# RAMPSdisplay.net
KiCad netlist of a schematic drawn in EAGLE
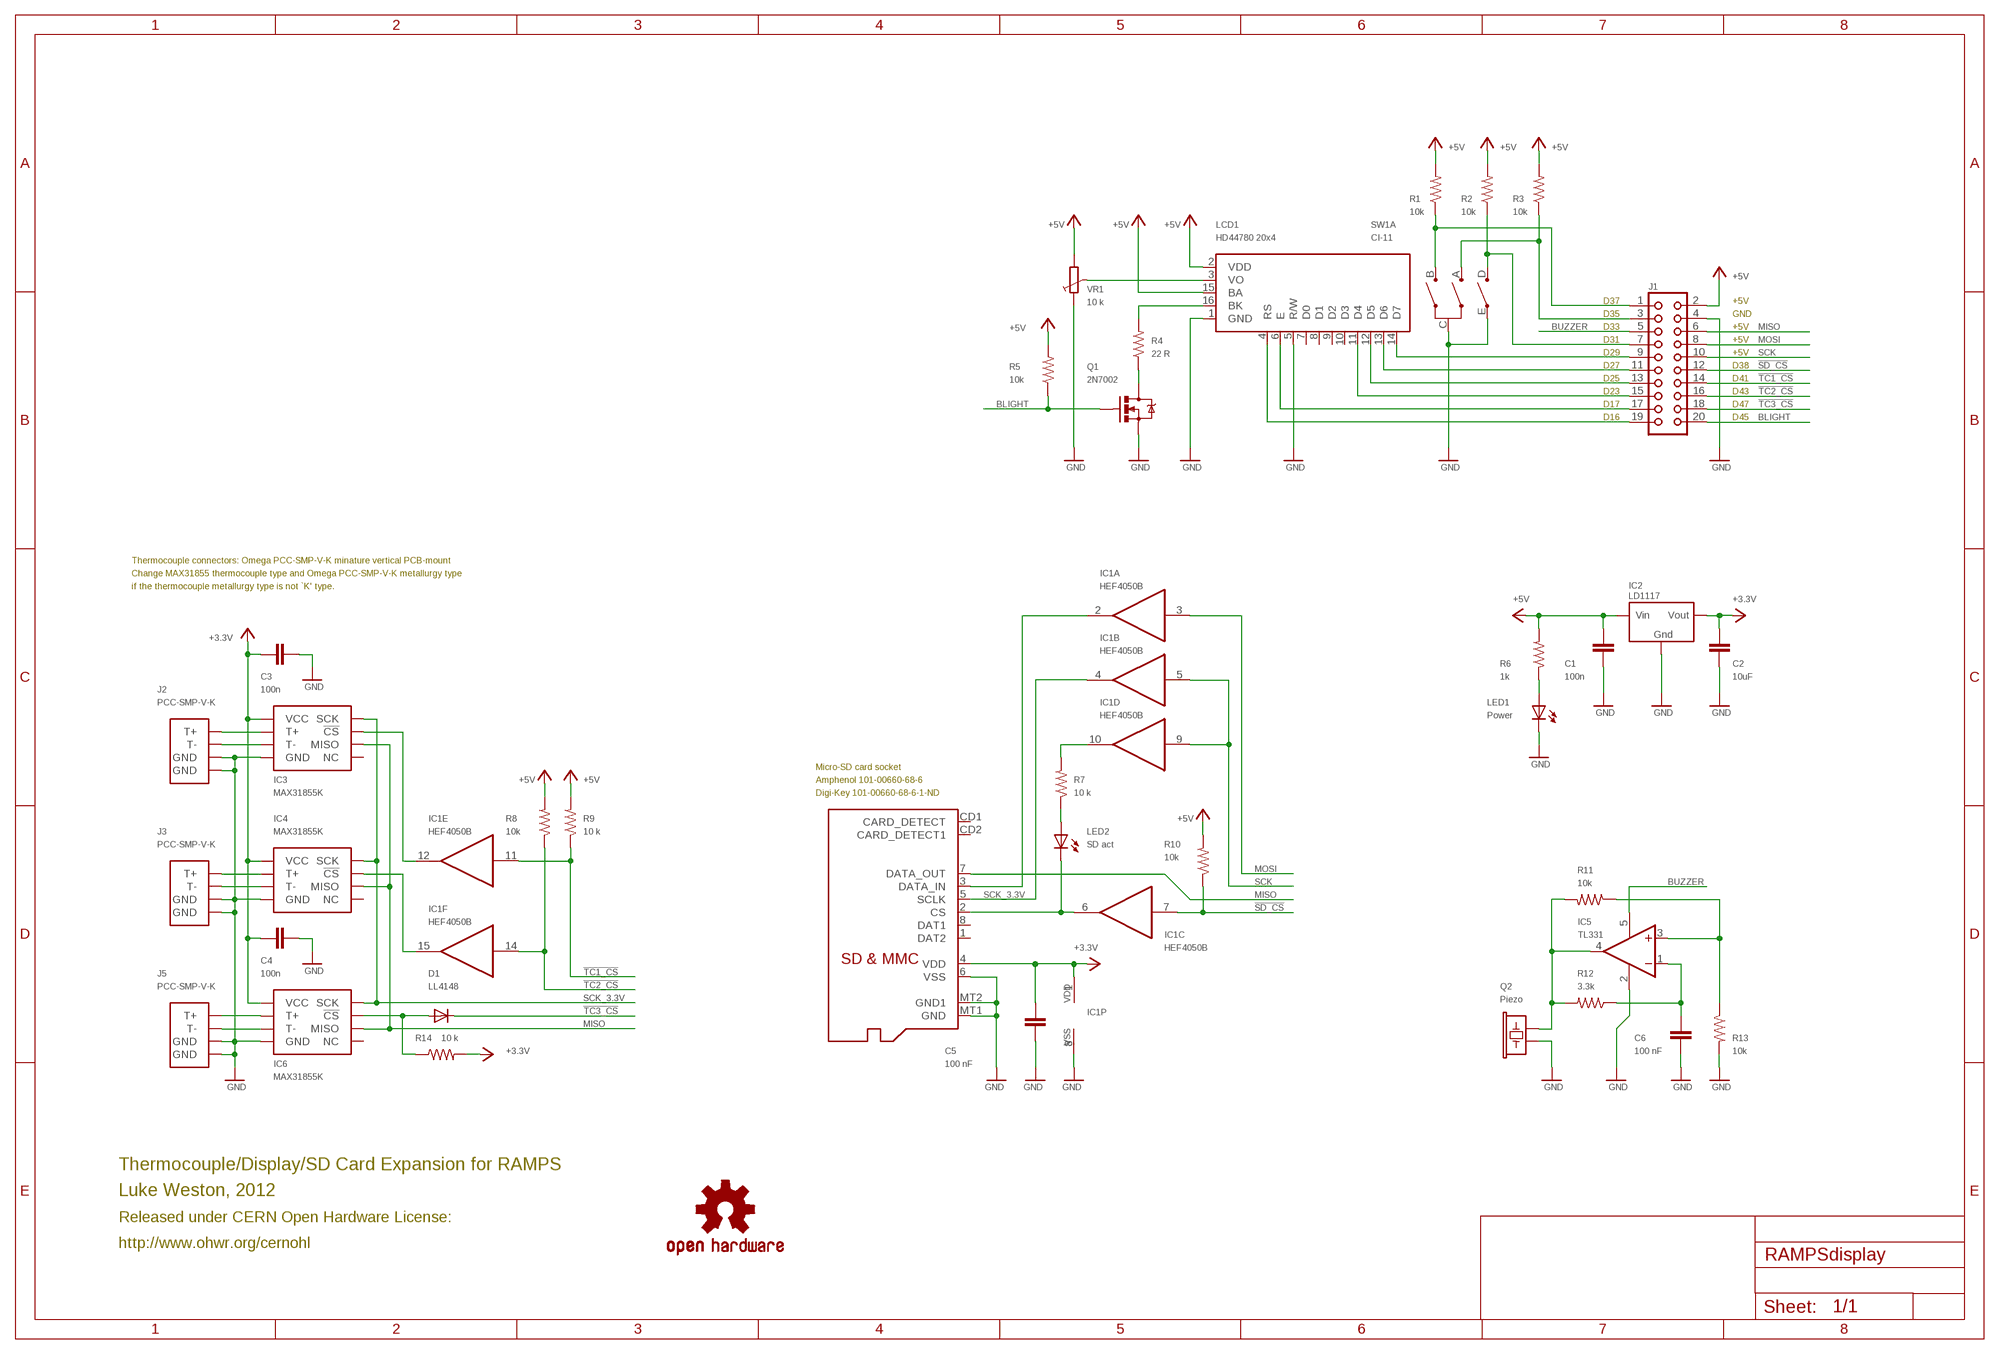
[diagram p0: schematic, sheet 1]

(export (version "E")
  (design (tool "Eeschema 10.0.6"))
  (components
    (comp (ref "C1")
      (value "100n")
      (footprint "eagle-import:C0805K")
      (libsource (lib "eagle-import") (part "C-EUC0805K"))
    )
    (comp (ref "C2")
      (value "10uF")
      (footprint "eagle-import:C0805K")
      (libsource (lib "eagle-import") (part "C-EUC0805K"))
    )
    (comp (ref "C3")
      (value "100n")
      (footprint "eagle-import:C0805K")
      (libsource (lib "eagle-import") (part "C-EUC0805K"))
    )
    (comp (ref "C4")
      (value "100n")
      (footprint "eagle-import:C0805K")
      (libsource (lib "eagle-import") (part "C-EUC0805K"))
    )
    (comp (ref "C5")
      (value "100 nF")
      (footprint "eagle-import:C0805K")
      (libsource (lib "eagle-import") (part "C-EUC0805K"))
    )
    (comp (ref "C6")
      (value "100 nF")
      (footprint "eagle-import:C0805K")
      (libsource (lib "eagle-import") (part "C-EUC0805K"))
    )
    (comp (ref "D1")
      (value "LL4148")
      (footprint "eagle-import:SOD80C")
      (libsource (lib "eagle-import") (part "DIODE-SOD80C"))
    )
    (comp (ref "IC1")
      (value "HEF4050B")
      (footprint "eagle-import:SO16")
      (libsource (lib "eagle-import") (part "4050D"))
    )
    (comp (ref "IC2")
      (value "LD1117")
      (footprint "eagle-import:SOT223")
      (fields (field (name "MPN") "REG1117"))
      (libsource (lib "eagle-import") (part "REG1117"))
    )
    (comp (ref "IC3")
      (value "MAX31855K")
      (footprint "eagle-import:MCLENG_SOIC-8")
      (libsource (lib "eagle-import") (part "MCLENG_MAX6675MAX31855"))
    )
    (comp (ref "IC4")
      (value "MAX31855K")
      (footprint "eagle-import:MCLENG_SOIC-8")
      (libsource (lib "eagle-import") (part "MCLENG_MAX6675MAX31855"))
    )
    (comp (ref "IC5")
      (value "TL331")
      (footprint "eagle-import:DBV-R-PDSO-G5")
      (libsource (lib "eagle-import") (part "TL331"))
    )
    (comp (ref "IC6")
      (value "MAX31855K")
      (footprint "eagle-import:MCLENG_SOIC-8")
      (libsource (lib "eagle-import") (part "MCLENG_MAX6675MAX31855"))
    )
    (comp (ref "J1")
      (value "CON20")
      (footprint "eagle-import:CON20")
      (libsource (lib "eagle-import") (part "CON20"))
    )
    (comp (ref "J2")
      (value "PCC-SMP-V-K")
      (footprint "eagle-import:MCLAUGHLINENG_TC_JACK")
      (libsource (lib "eagle-import") (part "MCLAUGHLINENG_TC_JACK"))
    )
    (comp (ref "J3")
      (value "PCC-SMP-V-K")
      (footprint "eagle-import:MCLAUGHLINENG_TC_JACK")
      (libsource (lib "eagle-import") (part "MCLAUGHLINENG_TC_JACK"))
    )
    (comp (ref "J4")
      (value "MicroSD Card")
      (footprint "eagle-import:ADAFRUIT_MICROSD")
      (libsource (lib "eagle-import") (part "ADAFRUIT_MICROSD"))
    )
    (comp (ref "J5")
      (value "PCC-SMP-V-K")
      (footprint "eagle-import:MCLAUGHLINENG_TC_JACK")
      (libsource (lib "eagle-import") (part "MCLAUGHLINENG_TC_JACK"))
    )
    (comp (ref "LCD1")
      (value "HD44780 20x4")
      (footprint "eagle-import:HDM20416L")
      (libsource (lib "eagle-import") (part "HDM20416L"))
    )
    (comp (ref "LED1")
      (value "Power")
      (footprint "eagle-import:CHIPLED_0805")
      (libsource (lib "eagle-import") (part "LEDCHIPLED_0805"))
    )
    (comp (ref "LED2")
      (value "SD act")
      (footprint "eagle-import:CHIPLED_0805")
      (libsource (lib "eagle-import") (part "LEDCHIPLED_0805"))
    )
    (comp (ref "Q1")
      (value "2N7002")
      (footprint "eagle-import:SOT23-3")
      (libsource (lib "eagle-import") (part "MOSFET-NCHANNELSMD"))
    )
    (comp (ref "Q2")
      (value "Piezo")
      (footprint "eagle-import:FREETRONICS-MASTER-V1_BUZZER-12X12-SMT")
      (libsource (lib "eagle-import") (part "FREETRONICS-MASTER-V1_BUZZERSMD12X12"))
    )
    (comp (ref "R1")
      (value "10k")
      (footprint "eagle-import:M0805")
      (libsource (lib "eagle-import") (part "R-US_M0805"))
    )
    (comp (ref "R2")
      (value "10k")
      (footprint "eagle-import:M0805")
      (libsource (lib "eagle-import") (part "R-US_M0805"))
    )
    (comp (ref "R3")
      (value "10k")
      (footprint "eagle-import:M0805")
      (libsource (lib "eagle-import") (part "R-US_M0805"))
    )
    (comp (ref "R4")
      (value "22 R")
      (footprint "eagle-import:M0805")
      (libsource (lib "eagle-import") (part "R-US_M0805"))
    )
    (comp (ref "R5")
      (value "10k")
      (footprint "eagle-import:M0805")
      (libsource (lib "eagle-import") (part "R-US_M0805"))
    )
    (comp (ref "R6")
      (value "1k")
      (footprint "eagle-import:M0805")
      (libsource (lib "eagle-import") (part "R-US_M0805"))
    )
    (comp (ref "R7")
      (value "10 k")
      (footprint "eagle-import:M0805")
      (libsource (lib "eagle-import") (part "R-US_M0805"))
    )
    (comp (ref "R8")
      (value "10k")
      (footprint "eagle-import:M0805")
      (libsource (lib "eagle-import") (part "R-US_M0805"))
    )
    (comp (ref "R9")
      (value "10 k")
      (footprint "eagle-import:M0805")
      (libsource (lib "eagle-import") (part "R-US_M0805"))
    )
    (comp (ref "R10")
      (value "10k")
      (footprint "eagle-import:M0805")
      (libsource (lib "eagle-import") (part "R-US_M0805"))
    )
    (comp (ref "R11")
      (value "10k")
      (footprint "eagle-import:M0805")
      (libsource (lib "eagle-import") (part "R-US_M0805"))
    )
    (comp (ref "R12")
      (value "3.3k")
      (footprint "eagle-import:M0805")
      (libsource (lib "eagle-import") (part "R-US_M0805"))
    )
    (comp (ref "R13")
      (value "10k")
      (footprint "eagle-import:M0805")
      (libsource (lib "eagle-import") (part "R-US_M0805"))
    )
    (comp (ref "R14")
      (value "10 k")
      (footprint "eagle-import:M0805")
      (libsource (lib "eagle-import") (part "R-US_M0805"))
    )
    (comp (ref "SW1")
      (value "CI-11")
      (footprint "eagle-import:CI-11")
      (libsource (lib "eagle-import") (part "CI-11"))
    )
    (comp (ref "U$")
      (value "OSHW-LOGOS")
      (footprint "eagle-import:OSHW-LOGO-S")
      (libsource (lib "eagle-import") (part "OSHW-LOGOS"))
    )
    (comp (ref "VR1")
      (value "10 k")
      (footprint "eagle-import:CT6")
      (libsource (lib "eagle-import") (part "TRIM_EU-CT6"))
    )
  )
  (nets
    (net (code "1") (name "+3.3V") (class "Default")
      (node (ref "C2") (pin "1") (pinfunction "1_1") (pintype "passive"))
      (node (ref "C3") (pin "1") (pinfunction "1_1") (pintype "passive"))
      (node (ref "C4") (pin "1") (pinfunction "1_1") (pintype "passive"))
      (node (ref "C5") (pin "1") (pinfunction "1_1") (pintype "passive"))
      (node (ref "IC1") (pin "1") (pinfunction "VDD_1") (pintype "power_in"))
      (node (ref "IC2") (pin "2") (pinfunction "VOUT_2") (pintype "output"))
      (node (ref "IC3") (pin "VCC") (pinfunction "VCC_VCC") (pintype "bidirectional"))
      (node (ref "IC4") (pin "VCC") (pinfunction "VCC_VCC") (pintype "bidirectional"))
      (node (ref "IC6") (pin "VCC") (pinfunction "VCC_VCC") (pintype "bidirectional"))
      (node (ref "J4") (pin "4") (pinfunction "VDD_4") (pintype "power_in"))
      (node (ref "R14") (pin "2") (pinfunction "2_2") (pintype "passive"))
    )
    (net (code "2") (name "+5V") (class "Default")
      (node (ref "C1") (pin "1") (pinfunction "1_1") (pintype "passive"))
      (node (ref "IC2") (pin "3") (pinfunction "VIN_3") (pintype "input"))
      (node (ref "J1") (pin "2") (pinfunction "2_2") (pintype "passive"))
      (node (ref "LCD1") (pin "15") (pinfunction "BA_15") (pintype "bidirectional"))
      (node (ref "LCD1") (pin "2") (pinfunction "VDD_2") (pintype "bidirectional"))
      (node (ref "R1") (pin "2") (pinfunction "2_2") (pintype "passive"))
      (node (ref "R10") (pin "2") (pinfunction "2_2") (pintype "passive"))
      (node (ref "R2") (pin "2") (pinfunction "2_2") (pintype "passive"))
      (node (ref "R3") (pin "2") (pinfunction "2_2") (pintype "passive"))
      (node (ref "R5") (pin "2") (pinfunction "2_2") (pintype "passive"))
      (node (ref "R6") (pin "2") (pinfunction "2_2") (pintype "passive"))
      (node (ref "R8") (pin "2") (pinfunction "2_2") (pintype "passive"))
      (node (ref "R9") (pin "2") (pinfunction "2_2") (pintype "passive"))
      (node (ref "VR1") (pin "A") (pinfunction "A_A") (pintype "passive"))
    )
    (net (code "3") (name "/BLIGHT") (class "Default")
      (node (ref "J1") (pin "20") (pinfunction "20_20") (pintype "passive"))
      (node (ref "Q1") (pin "1") (pinfunction "G_1") (pintype "passive"))
      (node (ref "R5") (pin "1") (pinfunction "1_1") (pintype "passive"))
    )
    (net (code "4") (name "/BUZZER") (class "Default")
      (node (ref "IC5") (pin "5") (pinfunction "V+_5") (pintype "power_in"))
      (node (ref "J1") (pin "5") (pinfunction "5_5") (pintype "passive"))
    )
    (net (code "5") (name "/MISO") (class "Default")
      (node (ref "IC3") (pin "SO") (pinfunction "MISO_SO") (pintype "bidirectional"))
      (node (ref "IC4") (pin "SO") (pinfunction "MISO_SO") (pintype "bidirectional"))
      (node (ref "IC6") (pin "SO") (pinfunction "MISO_SO") (pintype "bidirectional"))
      (node (ref "J1") (pin "6") (pinfunction "6_6") (pintype "passive"))
      (node (ref "J4") (pin "7") (pinfunction "DATA_OUT_7") (pintype "output"))
    )
    (net (code "6") (name "/MOSI") (class "Default")
      (node (ref "IC1") (pin "3") (pinfunction "I_3") (pintype "input"))
      (node (ref "J1") (pin "8") (pinfunction "8_8") (pintype "passive"))
    )
    (net (code "7") (name "/SCK") (class "Default")
      (node (ref "IC1") (pin "5") (pinfunction "I_5") (pintype "input"))
      (node (ref "IC1") (pin "9") (pinfunction "I_9") (pintype "input"))
      (node (ref "J1") (pin "10") (pinfunction "10_10") (pintype "passive"))
    )
    (net (code "8") (name "/SCK_3.3V") (class "Default")
      (node (ref "IC1") (pin "4") (pinfunction "O_4") (pintype "output"))
      (node (ref "IC3") (pin "SCK") (pinfunction "SCK_SCK") (pintype "bidirectional"))
      (node (ref "IC4") (pin "SCK") (pinfunction "SCK_SCK") (pintype "bidirectional"))
      (node (ref "IC6") (pin "SCK") (pinfunction "SCK_SCK") (pintype "bidirectional"))
      (node (ref "J4") (pin "5") (pinfunction "SCLK_5") (pintype "input"))
    )
    (net (code "9") (name "/~{SD_CS}") (class "Default")
      (node (ref "IC1") (pin "7") (pinfunction "I_7") (pintype "input"))
      (node (ref "J1") (pin "12") (pinfunction "12_12") (pintype "passive"))
      (node (ref "R10") (pin "1") (pinfunction "1_1") (pintype "passive"))
    )
    (net (code "10") (name "/~{TC1_CS}") (class "Default")
      (node (ref "IC1") (pin "11") (pinfunction "I_11") (pintype "input"))
      (node (ref "J1") (pin "14") (pinfunction "14_14") (pintype "passive"))
      (node (ref "R9") (pin "1") (pinfunction "1_1") (pintype "passive"))
    )
    (net (code "11") (name "/~{TC2_CS}") (class "Default")
      (node (ref "IC1") (pin "14") (pinfunction "I_14") (pintype "input"))
      (node (ref "J1") (pin "16") (pinfunction "16_16") (pintype "passive"))
      (node (ref "R8") (pin "1") (pinfunction "1_1") (pintype "passive"))
    )
    (net (code "12") (name "/~{TC3_CS}") (class "Default")
      (node (ref "D1") (pin "C") (pinfunction "C_C") (pintype "passive"))
      (node (ref "J1") (pin "18") (pinfunction "18_18") (pintype "passive"))
    )
    (net (code "13") (name "GND") (class "Default")
      (node (ref "C1") (pin "2") (pinfunction "2_2") (pintype "passive"))
      (node (ref "C2") (pin "2") (pinfunction "2_2") (pintype "passive"))
      (node (ref "C3") (pin "2") (pinfunction "2_2") (pintype "passive"))
      (node (ref "C4") (pin "2") (pinfunction "2_2") (pintype "passive"))
      (node (ref "C5") (pin "2") (pinfunction "2_2") (pintype "passive"))
      (node (ref "C6") (pin "2") (pinfunction "2_2") (pintype "passive"))
      (node (ref "IC1") (pin "8") (pinfunction "VSS_8") (pintype "power_in"))
      (node (ref "IC2") (pin "1") (pinfunction "GND_1") (pintype "power_in"))
      (node (ref "IC3") (pin "GND") (pinfunction "GND_GND") (pintype "bidirectional"))
      (node (ref "IC4") (pin "GND") (pinfunction "GND_GND") (pintype "bidirectional"))
      (node (ref "IC5") (pin "2") (pinfunction "GND_2") (pintype "power_in"))
      (node (ref "IC6") (pin "GND") (pinfunction "GND_GND") (pintype "bidirectional"))
      (node (ref "J1") (pin "4") (pinfunction "4_4") (pintype "passive"))
      (node (ref "J2") (pin "P$1") (pinfunction "GND_P$1") (pintype "bidirectional"))
      (node (ref "J2") (pin "P$2") (pinfunction "GND_P$2") (pintype "bidirectional"))
      (node (ref "J3") (pin "P$1") (pinfunction "GND_P$1") (pintype "bidirectional"))
      (node (ref "J3") (pin "P$2") (pinfunction "GND_P$2") (pintype "bidirectional"))
      (node (ref "J4") (pin "6") (pinfunction "VSS_6") (pintype "power_in"))
      (node (ref "J4") (pin "MT1") (pinfunction "GND_MT1") (pintype "power_in"))
      (node (ref "J4") (pin "MT2") (pinfunction "GND1_MT2") (pintype "power_in"))
      (node (ref "J5") (pin "P$1") (pinfunction "GND_P$1") (pintype "bidirectional"))
      (node (ref "J5") (pin "P$2") (pinfunction "GND_P$2") (pintype "bidirectional"))
      (node (ref "LCD1") (pin "1") (pinfunction "GND_1") (pintype "bidirectional"))
      (node (ref "LCD1") (pin "5") (pinfunction "R/W_5") (pintype "bidirectional"))
      (node (ref "LED1") (pin "C") (pinfunction "C_C") (pintype "passive"))
      (node (ref "Q1") (pin "2") (pinfunction "S_2") (pintype "passive"))
      (node (ref "Q2") (pin "1") (pinfunction "1_1") (pintype "passive"))
      (node (ref "R13") (pin "2") (pinfunction "2_2") (pintype "passive"))
      (node (ref "SW1") (pin "C") (pinfunction "C_C") (pintype "passive"))
      (node (ref "SW1") (pin "E") (pinfunction "E_E") (pintype "passive"))
      (node (ref "VR1") (pin "E") (pinfunction "E_E") (pintype "passive"))
    )
    (net (code "14") (name "Net-(IC1A-O)") (class "Default")
      (node (ref "IC1") (pin "2") (pinfunction "O_2") (pintype "output"))
      (node (ref "J4") (pin "3") (pinfunction "DATA_IN_3") (pintype "input"))
    )
    (net (code "15") (name "Net-(IC1C-O)") (class "Default")
      (node (ref "IC1") (pin "6") (pinfunction "O_6") (pintype "output"))
      (node (ref "J4") (pin "2") (pinfunction "CS_2") (pintype "input"))
      (node (ref "LED2") (pin "C") (pinfunction "C_C") (pintype "passive"))
    )
    (net (code "16") (name "Net-(IC1D-O)") (class "Default")
      (node (ref "IC1") (pin "10") (pinfunction "O_10") (pintype "output"))
      (node (ref "R7") (pin "2") (pinfunction "2_2") (pintype "passive"))
    )
    (net (code "17") (name "Net-(IC1E-O)") (class "Default")
      (node (ref "IC1") (pin "12") (pinfunction "O_12") (pintype "output"))
      (node (ref "IC3") (pin "CS") (pinfunction "~{CS}_CS") (pintype "bidirectional"))
    )
    (net (code "18") (name "Net-(IC1F-O)") (class "Default")
      (node (ref "IC1") (pin "15") (pinfunction "O_15") (pintype "output"))
      (node (ref "IC4") (pin "CS") (pinfunction "~{CS}_CS") (pintype "bidirectional"))
    )
    (net (code "19") (name "Net-(IC3-PadT+)") (class "Default")
      (node (ref "IC3") (pin "T+") (pinfunction "T+_T+") (pintype "bidirectional"))
      (node (ref "J2") (pin "T+") (pinfunction "T+_T+") (pintype "bidirectional"))
    )
    (net (code "20") (name "Net-(IC3-PadT-)") (class "Default")
      (node (ref "IC3") (pin "T-") (pinfunction "T-_T-") (pintype "bidirectional"))
      (node (ref "J2") (pin "T-") (pinfunction "T-_T-") (pintype "bidirectional"))
    )
    (net (code "21") (name "Net-(IC4-PadT+)") (class "Default")
      (node (ref "IC4") (pin "T+") (pinfunction "T+_T+") (pintype "bidirectional"))
      (node (ref "J3") (pin "T+") (pinfunction "T+_T+") (pintype "bidirectional"))
    )
    (net (code "22") (name "Net-(IC4-PadT-)") (class "Default")
      (node (ref "IC4") (pin "T-") (pinfunction "T-_T-") (pintype "bidirectional"))
      (node (ref "J3") (pin "T-") (pinfunction "T-_T-") (pintype "bidirectional"))
    )
    (net (code "23") (name "Net-(IC5-+IN)") (class "Default")
      (node (ref "IC5") (pin "3") (pinfunction "+IN_3") (pintype "input"))
      (node (ref "R11") (pin "1") (pinfunction "1_1") (pintype "passive"))
      (node (ref "R13") (pin "1") (pinfunction "1_1") (pintype "passive"))
    )
    (net (code "24") (name "Net-(IC5--IN)") (class "Default")
      (node (ref "C6") (pin "1") (pinfunction "1_1") (pintype "passive"))
      (node (ref "IC5") (pin "1") (pinfunction "-IN_1") (pintype "input"))
      (node (ref "R12") (pin "1") (pinfunction "1_1") (pintype "passive"))
    )
    (net (code "25") (name "Net-(IC5-OUT)") (class "Default")
      (node (ref "IC5") (pin "4") (pinfunction "OUT_4") (pintype "output"))
      (node (ref "Q2") (pin "2") (pinfunction "2_2") (pintype "passive"))
      (node (ref "R11") (pin "2") (pinfunction "2_2") (pintype "passive"))
      (node (ref "R12") (pin "2") (pinfunction "2_2") (pintype "passive"))
    )
    (net (code "26") (name "Net-(IC6-PadT+)") (class "Default")
      (node (ref "IC6") (pin "T+") (pinfunction "T+_T+") (pintype "bidirectional"))
      (node (ref "J5") (pin "T+") (pinfunction "T+_T+") (pintype "bidirectional"))
    )
    (net (code "27") (name "Net-(IC6-PadT-)") (class "Default")
      (node (ref "IC6") (pin "T-") (pinfunction "T-_T-") (pintype "bidirectional"))
      (node (ref "J5") (pin "T-") (pinfunction "T-_T-") (pintype "bidirectional"))
    )
    (net (code "28") (name "Net-(IC6-~{CS})") (class "Default")
      (node (ref "D1") (pin "A") (pinfunction "A_A") (pintype "passive"))
      (node (ref "IC6") (pin "CS") (pinfunction "~{CS}_CS") (pintype "bidirectional"))
      (node (ref "R14") (pin "1") (pinfunction "1_1") (pintype "passive"))
    )
    (net (code "29") (name "Net-(J1-Pad1)") (class "Default")
      (node (ref "J1") (pin "1") (pinfunction "1_1") (pintype "passive"))
      (node (ref "R1") (pin "1") (pinfunction "1_1") (pintype "passive"))
      (node (ref "SW1") (pin "B") (pinfunction "B_B") (pintype "passive"))
    )
    (net (code "30") (name "Net-(J1-Pad3)") (class "Default")
      (node (ref "J1") (pin "3") (pinfunction "3_3") (pintype "passive"))
      (node (ref "R3") (pin "1") (pinfunction "1_1") (pintype "passive"))
      (node (ref "SW1") (pin "A") (pinfunction "A_A") (pintype "passive"))
    )
    (net (code "31") (name "Net-(J1-Pad7)") (class "Default")
      (node (ref "J1") (pin "7") (pinfunction "7_7") (pintype "passive"))
      (node (ref "R2") (pin "1") (pinfunction "1_1") (pintype "passive"))
      (node (ref "SW1") (pin "D") (pinfunction "D_D") (pintype "passive"))
    )
    (net (code "32") (name "Net-(LCD1-BK)") (class "Default")
      (node (ref "LCD1") (pin "16") (pinfunction "BK_16") (pintype "bidirectional"))
      (node (ref "R4") (pin "2") (pinfunction "2_2") (pintype "passive"))
    )
    (net (code "33") (name "Net-(LCD1-D4)") (class "Default")
      (node (ref "J1") (pin "15") (pinfunction "15_15") (pintype "passive"))
      (node (ref "LCD1") (pin "11") (pinfunction "D4_11") (pintype "bidirectional"))
    )
    (net (code "34") (name "Net-(LCD1-D5)") (class "Default")
      (node (ref "J1") (pin "13") (pinfunction "13_13") (pintype "passive"))
      (node (ref "LCD1") (pin "12") (pinfunction "D5_12") (pintype "bidirectional"))
    )
    (net (code "35") (name "Net-(LCD1-D6)") (class "Default")
      (node (ref "J1") (pin "11") (pinfunction "11_11") (pintype "passive"))
      (node (ref "LCD1") (pin "13") (pinfunction "D6_13") (pintype "bidirectional"))
    )
    (net (code "36") (name "Net-(LCD1-D7)") (class "Default")
      (node (ref "J1") (pin "9") (pinfunction "9_9") (pintype "passive"))
      (node (ref "LCD1") (pin "14") (pinfunction "D7_14") (pintype "bidirectional"))
    )
    (net (code "37") (name "Net-(LCD1-E)") (class "Default")
      (node (ref "J1") (pin "17") (pinfunction "17_17") (pintype "passive"))
      (node (ref "LCD1") (pin "6") (pinfunction "E_6") (pintype "bidirectional"))
    )
    (net (code "38") (name "Net-(LCD1-RS)") (class "Default")
      (node (ref "J1") (pin "19") (pinfunction "19_19") (pintype "passive"))
      (node (ref "LCD1") (pin "4") (pinfunction "RS_4") (pintype "bidirectional"))
    )
    (net (code "39") (name "Net-(LCD1-VO)") (class "Default")
      (node (ref "LCD1") (pin "3") (pinfunction "VO_3") (pintype "bidirectional"))
      (node (ref "VR1") (pin "S") (pinfunction "S_S") (pintype "passive"))
    )
    (net (code "40") (name "Net-(LED1-PadA)") (class "Default")
      (node (ref "LED1") (pin "A") (pinfunction "A_A") (pintype "passive"))
      (node (ref "R6") (pin "1") (pinfunction "1_1") (pintype "passive"))
    )
    (net (code "41") (name "Net-(LED2-PadA)") (class "Default")
      (node (ref "LED2") (pin "A") (pinfunction "A_A") (pintype "passive"))
      (node (ref "R7") (pin "1") (pinfunction "1_1") (pintype "passive"))
    )
    (net (code "42") (name "Net-(Q1-D)") (class "Default")
      (node (ref "Q1") (pin "3") (pinfunction "D_3") (pintype "passive"))
      (node (ref "R4") (pin "1") (pinfunction "1_1") (pintype "passive"))
    )
    (net (code "43") (name "unconnected-(IC3-PadNC)") (class "Default")
      (node (ref "IC3") (pin "NC") (pinfunction "NC_NC") (pintype "no_connect"))
    )
    (net (code "44") (name "unconnected-(IC4-PadNC)") (class "Default")
      (node (ref "IC4") (pin "NC") (pinfunction "NC_NC") (pintype "no_connect"))
    )
    (net (code "45") (name "unconnected-(IC6-PadNC)") (class "Default")
      (node (ref "IC6") (pin "NC") (pinfunction "NC_NC") (pintype "no_connect"))
    )
    (net (code "46") (name "unconnected-(J4-CARD_DETECT-PadCD1)") (class "Default")
      (node (ref "J4") (pin "CD1") (pinfunction "CARD_DETECT_CD1") (pintype "passive"))
    )
    (net (code "47") (name "unconnected-(J4-CARD_DETECT1-PadCD2)") (class "Default")
      (node (ref "J4") (pin "CD2") (pinfunction "CARD_DETECT1_CD2") (pintype "passive"))
    )
    (net (code "48") (name "unconnected-(J4-DAT1-Pad8)") (class "Default")
      (node (ref "J4") (pin "8") (pinfunction "DAT1_8") (pintype "bidirectional"))
    )
    (net (code "49") (name "unconnected-(J4-DAT2-Pad1)") (class "Default")
      (node (ref "J4") (pin "1") (pinfunction "DAT2_1") (pintype "bidirectional"))
    )
    (net (code "50") (name "unconnected-(LCD1-D0-Pad7)") (class "Default")
      (node (ref "LCD1") (pin "7") (pinfunction "D0_7") (pintype "bidirectional"))
    )
    (net (code "51") (name "unconnected-(LCD1-D1-Pad8)") (class "Default")
      (node (ref "LCD1") (pin "8") (pinfunction "D1_8") (pintype "bidirectional"))
    )
    (net (code "52") (name "unconnected-(LCD1-D2-Pad9)") (class "Default")
      (node (ref "LCD1") (pin "9") (pinfunction "D2_9") (pintype "bidirectional"))
    )
    (net (code "53") (name "unconnected-(LCD1-D3-Pad10)") (class "Default")
      (node (ref "LCD1") (pin "10") (pinfunction "D3_10") (pintype "bidirectional"))
    )
  )
)
